# WiFiHumi.net
KiCad netlist of a schematic drawn in EAGLE
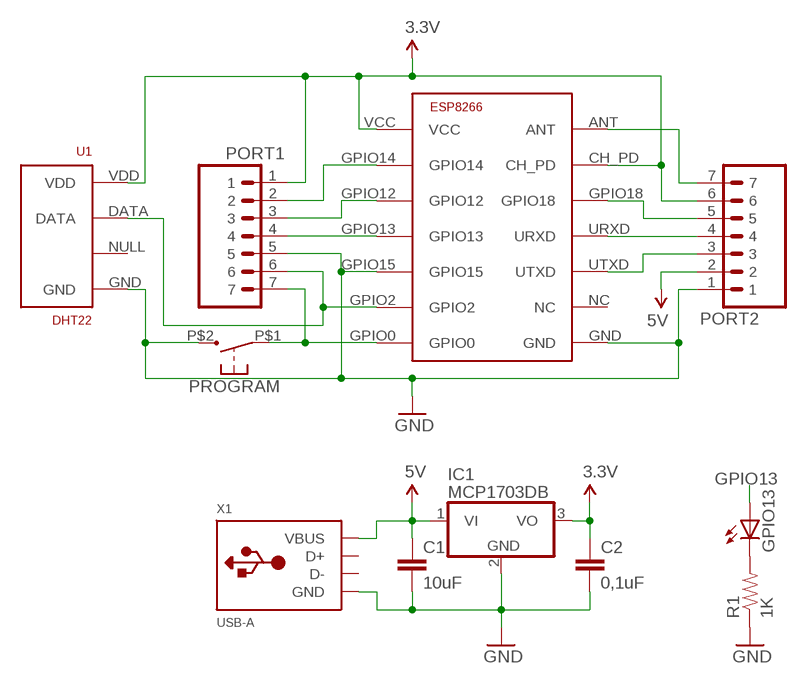
[diagram p0: schematic, sheet 1]

(export (version "E")
  (design (tool "Eeschema 10.0.6"))
  (components
    (comp (ref "C1")
      (value "10uF")
      (footprint "eagle-import:0603-CAP")
      (libsource (lib "eagle-import") (part "CAP0603-CAP"))
    )
    (comp (ref "C2")
      (value "0,1uF")
      (footprint "eagle-import:0603-CAP")
      (libsource (lib "eagle-import") (part "CAP0603-CAP"))
    )
    (comp (ref "GPIO13")
      (value "LEDCHIPLED_0603")
      (footprint "eagle-import:CHIPLED_0603")
      (libsource (lib "eagle-import") (part "LEDCHIPLED_0603"))
    )
    (comp (ref "IC1")
      (value "MCP1703DB")
      (footprint "eagle-import:SOT223")
      (libsource (lib "eagle-import") (part "MCP1703DB"))
    )
    (comp (ref "PORT1")
      (value "DIPLOCK7-FEMALE")
      (footprint "eagle-import:1X07_FEMALE_LOCK.010")
      (libsource (lib "eagle-import") (part "DIPLOCK7-FEMALE"))
    )
    (comp (ref "PORT2")
      (value "DIPLOCK7-FEMALE")
      (footprint "eagle-import:1X07_FEMALE_LOCK.010")
      (libsource (lib "eagle-import") (part "DIPLOCK7-FEMALE"))
    )
    (comp (ref "PROGRAM")
      (value "OMRON_B3U-1000_TACT_SW")
      (footprint "eagle-import:BC3-1000")
      (libsource (lib "eagle-import") (part "OMRON_B3U-1000_TACT_SW"))
    )
    (comp (ref "R1")
      (value "1K")
      (footprint "eagle-import:0603-RES")
      (libsource (lib "eagle-import") (part "RESISTOR0603-RES"))
    )
    (comp (ref "U$1")
      (value "ESP8266")
      (footprint "eagle-import:ESP-03")
      (libsource (lib "eagle-import") (part "ESP8266"))
    )
    (comp (ref "U1")
      (value "DHT22")
      (footprint "eagle-import:RHT03_DHT-22_RA")
      (libsource (lib "eagle-import") (part "RHT03_DHT-22_AM2302RA"))
    )
    (comp (ref "X1")
      (value "USB-A")
      (footprint "eagle-import:MOLEX_480371000")
      (libsource (lib "eagle-import") (part "USB-A"))
    )
  )
  (nets
    (net (code "1") (name "/GPIO13") (class "Default")
      (node (ref "GPIO13") (pin "A") (pinfunction "A_A") (pintype "passive"))
      (node (ref "PORT1") (pin "4") (pinfunction "4_4") (pintype "power_in"))
      (node (ref "U$1") (pin "GPIO13") (pinfunction "GPIO13_GPIO13") (pintype "bidirectional"))
    )
    (net (code "2") (name "3.3V") (class "Default")
      (node (ref "C2") (pin "1") (pinfunction "1_1") (pintype "passive"))
      (node (ref "IC1") (pin "3") (pinfunction "VO_3") (pintype "passive"))
      (node (ref "PORT1") (pin "1") (pinfunction "1_1") (pintype "bidirectional"))
      (node (ref "PORT2") (pin "6") (pinfunction "6_6") (pintype "power_in"))
      (node (ref "U$1") (pin "CH_PD") (pinfunction "CH_PD_CH_PD") (pintype "bidirectional"))
      (node (ref "U$1") (pin "VCC") (pinfunction "VCC_VCC") (pintype "bidirectional"))
      (node (ref "U1") (pin "VDD") (pinfunction "VDD_VDD") (pintype "power_in"))
    )
    (net (code "3") (name "5V") (class "Default")
      (node (ref "C1") (pin "1") (pinfunction "1_1") (pintype "passive"))
      (node (ref "IC1") (pin "1") (pinfunction "VI_1") (pintype "input"))
      (node (ref "PORT2") (pin "2") (pinfunction "2_2") (pintype "bidirectional"))
      (node (ref "X1") (pin "1") (pinfunction "VBUS_1") (pintype "power_in"))
    )
    (net (code "4") (name "GND") (class "Default")
      (node (ref "C1") (pin "2") (pinfunction "2_2") (pintype "passive"))
      (node (ref "C2") (pin "2") (pinfunction "2_2") (pintype "passive"))
      (node (ref "IC1") (pin "2") (pinfunction "GND_2") (pintype "passive"))
      (node (ref "PORT1") (pin "5") (pinfunction "5_5") (pintype "bidirectional"))
      (node (ref "PORT2") (pin "1") (pinfunction "1_1") (pintype "bidirectional"))
      (node (ref "PROGRAM") (pin "P$2") (pinfunction "3_P$2") (pintype "passive"))
      (node (ref "R1") (pin "1") (pinfunction "1_1") (pintype "passive"))
      (node (ref "U$1") (pin "GND") (pinfunction "GND_GND") (pintype "bidirectional"))
      (node (ref "U$1") (pin "GPIO15") (pinfunction "GPIO15_GPIO15") (pintype "bidirectional"))
      (node (ref "U1") (pin "GND") (pinfunction "GND_GND") (pintype "power_in"))
      (node (ref "X1") (pin "4") (pinfunction "GND_4") (pintype "power_in"))
    )
    (net (code "5") (name "Net-(GPIO13-PadC)") (class "Default")
      (node (ref "GPIO13") (pin "C") (pinfunction "C_C") (pintype "passive"))
      (node (ref "R1") (pin "2") (pinfunction "2_2") (pintype "passive"))
    )
    (net (code "6") (name "Net-(PORT1-Pad2)") (class "Default")
      (node (ref "PORT1") (pin "2") (pinfunction "2_2") (pintype "bidirectional"))
      (node (ref "U$1") (pin "GPIO14") (pinfunction "GPIO14_GPIO14") (pintype "bidirectional"))
    )
    (net (code "7") (name "Net-(PORT1-Pad3)") (class "Default")
      (node (ref "PORT1") (pin "3") (pinfunction "3_3") (pintype "power_in"))
      (node (ref "U$1") (pin "GPIO12") (pinfunction "GPIO12_GPIO12") (pintype "bidirectional"))
    )
    (net (code "8") (name "Net-(PORT1-Pad6)") (class "Default")
      (node (ref "PORT1") (pin "6") (pinfunction "6_6") (pintype "power_in"))
      (node (ref "U$1") (pin "GPIO2") (pinfunction "GPIO2_GPIO2") (pintype "bidirectional"))
      (node (ref "U1") (pin "DATA") (pinfunction "DATA_DATA") (pintype "bidirectional"))
    )
    (net (code "9") (name "Net-(PORT2-Pad3)") (class "Default")
      (node (ref "PORT2") (pin "3") (pinfunction "3_3") (pintype "power_in"))
      (node (ref "U$1") (pin "UTXD") (pinfunction "UTXD_UTXD") (pintype "bidirectional"))
    )
    (net (code "10") (name "Net-(PORT2-Pad4)") (class "Default")
      (node (ref "PORT2") (pin "4") (pinfunction "4_4") (pintype "power_in"))
      (node (ref "U$1") (pin "URXD") (pinfunction "URXD_URXD") (pintype "bidirectional"))
    )
    (net (code "11") (name "Net-(PORT2-Pad5)") (class "Default")
      (node (ref "PORT2") (pin "5") (pinfunction "5_5") (pintype "bidirectional"))
      (node (ref "U$1") (pin "GPIO18") (pinfunction "GPIO18_GPIO18") (pintype "bidirectional"))
    )
    (net (code "12") (name "Net-(PORT2-Pad7)") (class "Default")
      (node (ref "PORT2") (pin "7") (pinfunction "7_7") (pintype "bidirectional"))
      (node (ref "U$1") (pin "ANT") (pinfunction "ANT_ANT") (pintype "bidirectional"))
    )
    (net (code "13") (name "Net-(PROGRAM-1)") (class "Default")
      (node (ref "PORT1") (pin "7") (pinfunction "7_7") (pintype "bidirectional"))
      (node (ref "PROGRAM") (pin "P$1") (pinfunction "1_P$1") (pintype "passive"))
      (node (ref "U$1") (pin "GPIO0") (pinfunction "GPIO0_GPIO0") (pintype "bidirectional"))
    )
    (net (code "14") (name "unconnected-(U$1-PadNC)") (class "Default")
      (node (ref "U$1") (pin "NC") (pinfunction "NC_NC") (pintype "bidirectional"))
    )
    (net (code "15") (name "unconnected-(U1-PadNULL)") (class "Default")
      (node (ref "U1") (pin "NULL") (pinfunction "NULL_NULL") (pintype "no_connect"))
    )
    (net (code "16") (name "unconnected-(X1-D+-Pad3)") (class "Default")
      (node (ref "X1") (pin "3") (pinfunction "D+_3") (pintype "bidirectional"))
    )
    (net (code "17") (name "unconnected-(X1-D--Pad2)") (class "Default")
      (node (ref "X1") (pin "2") (pinfunction "D-_2") (pintype "bidirectional"))
    )
  )
)
